# BUTTONS.net
KiCad netlist of a schematic drawn in Altium Designer
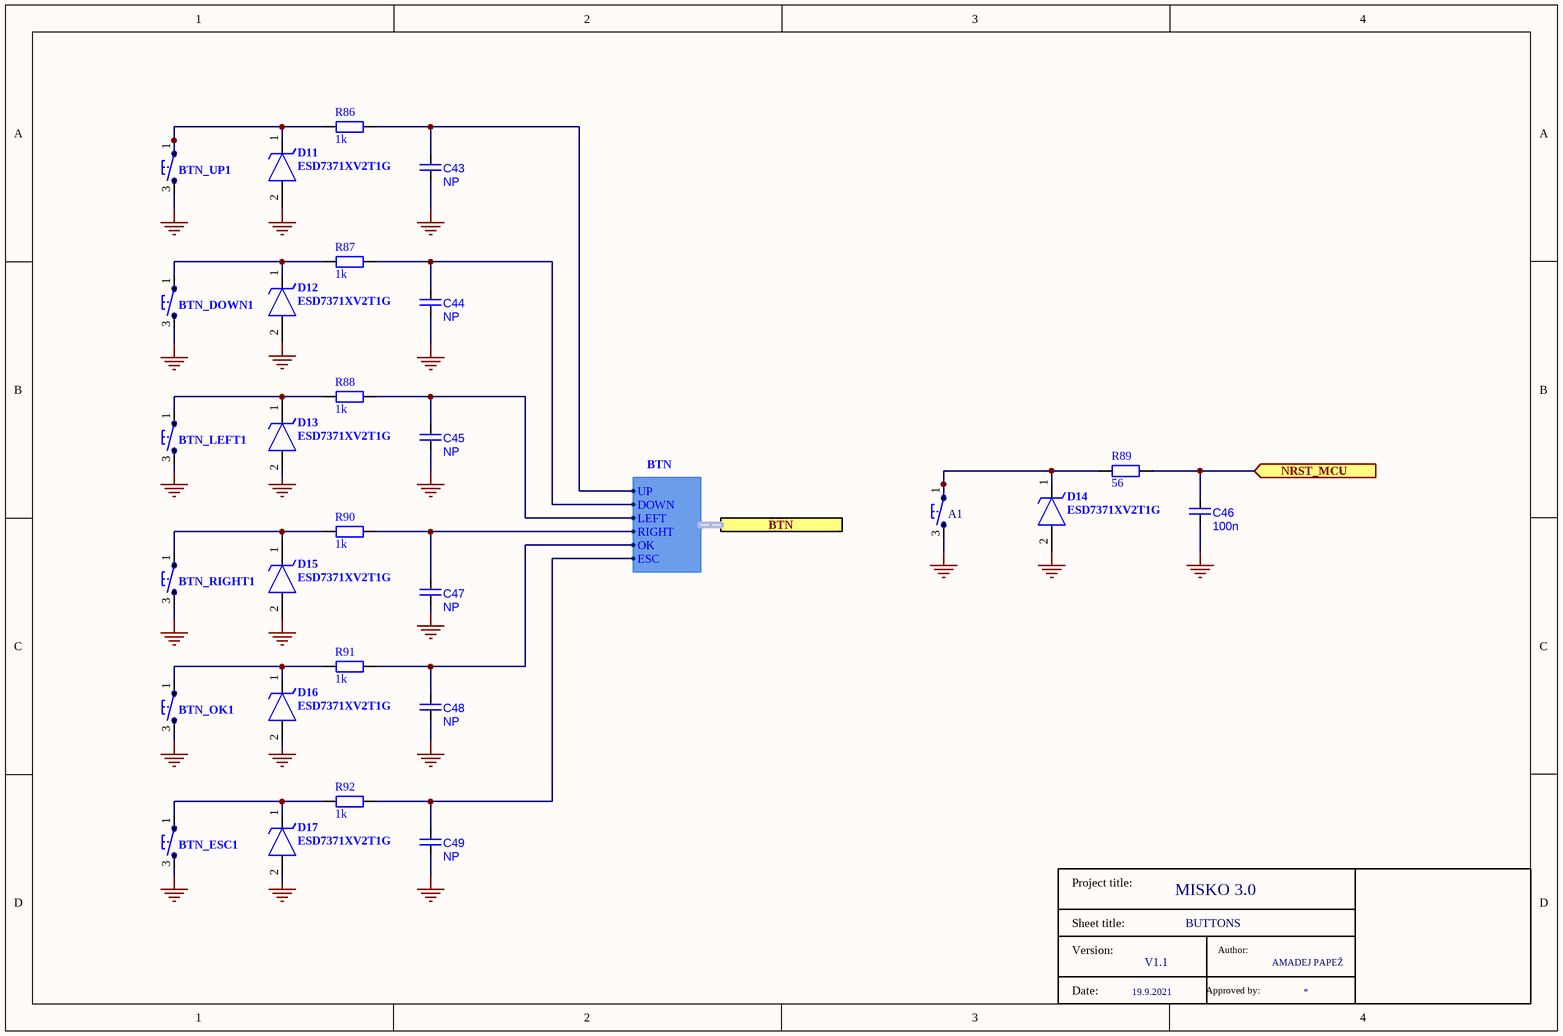
[diagram p0: BUTTONS.SchDoc]

(export (version "E")
  (design (tool "Eeschema 10.0.6"))
  (components
    (comp (ref "A1")
      (value "Button_6x6")
      (footprint "Tipka 6x6")
      (description "Tactile switch SMD")
      (libsource (lib "MISKO3_V6") (part "Button_6x6"))
    )
    (comp (ref "BTN_DOWN1")
      (value "Button_6x6")
      (footprint "Tipka 6x6")
      (description "Tactile switch SMD")
      (libsource (lib "MISKO3_V6") (part "Button_6x6"))
    )
    (comp (ref "BTN_ESC1")
      (value "Button_6x6")
      (footprint "Tipka 6x6")
      (description "Tactile switch SMD")
      (libsource (lib "MISKO3_V6") (part "Button_6x6"))
    )
    (comp (ref "BTN_LEFT1")
      (value "Button_6x6")
      (footprint "Tipka 6x6")
      (description "Tactile switch SMD")
      (libsource (lib "MISKO3_V6") (part "Button_6x6"))
    )
    (comp (ref "BTN_OK1")
      (value "Button_6x6")
      (footprint "Tipka 6x6")
      (description "Tactile switch SMD")
      (libsource (lib "MISKO3_V6") (part "Button_6x6"))
    )
    (comp (ref "BTN_RIGHT1")
      (value "Button_6x6")
      (footprint "Tipka 6x6")
      (description "Tactile switch SMD")
      (libsource (lib "MISKO3_V6") (part "Button_6x6"))
    )
    (comp (ref "BTN_UP1")
      (value "Button_6x6")
      (footprint "Tipka 6x6")
      (description "Tactile switch SMD")
      (libsource (lib "MISKO3_V6") (part "Button_6x6"))
    )
    (comp (ref "C43")
      (value "NP")
      (footprint "C0603")
      (description "Capacitor")
      (libsource (lib "MISKO3_V6") (part "C"))
    )
    (comp (ref "C44")
      (value "NP")
      (footprint "C0603")
      (description "Capacitor")
      (libsource (lib "MISKO3_V6") (part "C"))
    )
    (comp (ref "C45")
      (value "NP")
      (footprint "C0603")
      (description "Capacitor")
      (libsource (lib "MISKO3_V6") (part "C"))
    )
    (comp (ref "C46")
      (value "100n")
      (footprint "C0603")
      (description "Capacitor")
      (libsource (lib "MISKO3_V6") (part "C"))
    )
    (comp (ref "C47")
      (value "NP")
      (footprint "C0603")
      (description "Capacitor")
      (libsource (lib "MISKO3_V6") (part "C"))
    )
    (comp (ref "C48")
      (value "NP")
      (footprint "C0603")
      (description "Capacitor")
      (libsource (lib "MISKO3_V6") (part "C"))
    )
    (comp (ref "C49")
      (value "NP")
      (footprint "C0603")
      (description "Capacitor")
      (libsource (lib "MISKO3_V6") (part "C"))
    )
    (comp (ref "D11")
      (value "ESD7371XV2T1G")
      (footprint "SOD1608X70N")
      (description "TVS Diode (Uni-directional)")
      (fields (field (name "MOUSER PART NUMBER") "863-ESD7371XV2T1G"))
      (libsource (lib "MISKO3_V6") (part "ESD7371XV2T1G"))
    )
    (comp (ref "D12")
      (value "ESD7371XV2T1G")
      (footprint "SOD1608X70N")
      (description "TVS Diode (Uni-directional)")
      (fields (field (name "MOUSER PART NUMBER") "863-ESD7371XV2T1G"))
      (libsource (lib "MISKO3_V6") (part "ESD7371XV2T1G"))
    )
    (comp (ref "D13")
      (value "ESD7371XV2T1G")
      (footprint "SOD1608X70N")
      (description "TVS Diode (Uni-directional)")
      (fields (field (name "MOUSER PART NUMBER") "863-ESD7371XV2T1G"))
      (libsource (lib "MISKO3_V6") (part "ESD7371XV2T1G"))
    )
    (comp (ref "D14")
      (value "ESD7371XV2T1G")
      (footprint "SOD1608X70N")
      (description "TVS Diode (Uni-directional)")
      (fields (field (name "MOUSER PART NUMBER") "863-ESD7371XV2T1G"))
      (libsource (lib "MISKO3_V6") (part "ESD7371XV2T1G"))
    )
    (comp (ref "D15")
      (value "ESD7371XV2T1G")
      (footprint "SOD1608X70N")
      (description "TVS Diode (Uni-directional)")
      (fields (field (name "MOUSER PART NUMBER") "863-ESD7371XV2T1G"))
      (libsource (lib "MISKO3_V6") (part "ESD7371XV2T1G"))
    )
    (comp (ref "D16")
      (value "ESD7371XV2T1G")
      (footprint "SOD1608X70N")
      (description "TVS Diode (Uni-directional)")
      (fields (field (name "MOUSER PART NUMBER") "863-ESD7371XV2T1G"))
      (libsource (lib "MISKO3_V6") (part "ESD7371XV2T1G"))
    )
    (comp (ref "D17")
      (value "ESD7371XV2T1G")
      (footprint "SOD1608X70N")
      (description "TVS Diode (Uni-directional)")
      (fields (field (name "MOUSER PART NUMBER") "863-ESD7371XV2T1G"))
      (libsource (lib "MISKO3_V6") (part "ESD7371XV2T1G"))
    )
    (comp (ref "R86")
      (value "1k")
      (footprint "R1608_0603I_L")
      (description "R")
      (libsource (lib "MISKO3_V6") (part "R"))
    )
    (comp (ref "R87")
      (value "1k")
      (footprint "R1608_0603I_L")
      (description "R")
      (libsource (lib "MISKO3_V6") (part "R"))
    )
    (comp (ref "R88")
      (value "1k")
      (footprint "R1608_0603I_L")
      (description "R")
      (libsource (lib "MISKO3_V6") (part "R"))
    )
    (comp (ref "R89")
      (value "56")
      (footprint "R1608_0603I_L")
      (description "R")
      (libsource (lib "MISKO3_V6") (part "R"))
    )
    (comp (ref "R90")
      (value "1k")
      (footprint "R1608_0603I_L")
      (description "R")
      (libsource (lib "MISKO3_V6") (part "R"))
    )
    (comp (ref "R91")
      (value "1k")
      (footprint "R1608_0603I_L")
      (description "R")
      (libsource (lib "MISKO3_V6") (part "R"))
    )
    (comp (ref "R92")
      (value "1k")
      (footprint "R1608_0603I_L")
      (description "R")
      (libsource (lib "MISKO3_V6") (part "R"))
    )
    (comp (ref "T10") (value "~") (libsource (lib "MISKO3_V6") (part "Title block")))
  )
  (nets
    (net (code "2") (name "/NRST_MCU") (class "Default")
      (node (ref "C46") (pin "2") (pinfunction "2_2") (pintype "passive"))
      (node (ref "R89") (pin "1") (pintype "passive"))
    )
    (net (code "4") (name "GND") (class "Default")
      (node (ref "A1") (pin "3") (pinfunction "3_3") (pintype "passive"))
      (node (ref "BTN_DOWN1") (pin "3") (pinfunction "3_3") (pintype "passive"))
      (node (ref "BTN_ESC1") (pin "3") (pinfunction "3_3") (pintype "passive"))
      (node (ref "BTN_LEFT1") (pin "3") (pinfunction "3_3") (pintype "passive"))
      (node (ref "BTN_OK1") (pin "3") (pinfunction "3_3") (pintype "passive"))
      (node (ref "BTN_RIGHT1") (pin "3") (pinfunction "3_3") (pintype "passive"))
      (node (ref "BTN_UP1") (pin "3") (pinfunction "3_3") (pintype "passive"))
      (node (ref "C43") (pin "1") (pinfunction "1_1") (pintype "passive"))
      (node (ref "C44") (pin "1") (pinfunction "1_1") (pintype "passive"))
      (node (ref "C45") (pin "1") (pinfunction "1_1") (pintype "passive"))
      (node (ref "C46") (pin "1") (pinfunction "1_1") (pintype "passive"))
      (node (ref "C47") (pin "1") (pinfunction "1_1") (pintype "passive"))
      (node (ref "C48") (pin "1") (pinfunction "1_1") (pintype "passive"))
      (node (ref "C49") (pin "1") (pinfunction "1_1") (pintype "passive"))
      (node (ref "D11") (pin "2") (pinfunction "A_2") (pintype "passive"))
      (node (ref "D12") (pin "2") (pinfunction "A_2") (pintype "passive"))
      (node (ref "D13") (pin "2") (pinfunction "A_2") (pintype "passive"))
      (node (ref "D14") (pin "2") (pinfunction "A_2") (pintype "passive"))
      (node (ref "D15") (pin "2") (pinfunction "A_2") (pintype "passive"))
      (node (ref "D16") (pin "2") (pinfunction "A_2") (pintype "passive"))
      (node (ref "D17") (pin "2") (pinfunction "A_2") (pintype "passive"))
    )
    (net (code "5") (name "Net-(C43-Pad2)") (class "Default")
      (node (ref "C43") (pin "2") (pinfunction "2_2") (pintype "passive"))
      (node (ref "R86") (pin "1") (pintype "passive"))
    )
    (net (code "6") (name "Net-(C44-Pad2)") (class "Default")
      (node (ref "C44") (pin "2") (pinfunction "2_2") (pintype "passive"))
      (node (ref "R87") (pin "1") (pintype "passive"))
    )
    (net (code "7") (name "Net-(C45-Pad2)") (class "Default")
      (node (ref "C45") (pin "2") (pinfunction "2_2") (pintype "passive"))
      (node (ref "R88") (pin "1") (pintype "passive"))
    )
    (net (code "8") (name "Net-(C47-Pad2)") (class "Default")
      (node (ref "C47") (pin "2") (pinfunction "2_2") (pintype "passive"))
      (node (ref "R90") (pin "1") (pintype "passive"))
    )
    (net (code "9") (name "Net-(C48-Pad2)") (class "Default")
      (node (ref "C48") (pin "2") (pinfunction "2_2") (pintype "passive"))
      (node (ref "R91") (pin "1") (pintype "passive"))
    )
    (net (code "10") (name "Net-(C49-Pad2)") (class "Default")
      (node (ref "C49") (pin "2") (pinfunction "2_2") (pintype "passive"))
      (node (ref "R92") (pin "1") (pintype "passive"))
    )
    (net (code "11") (name "Net-(D11-K)") (class "Default")
      (node (ref "BTN_UP1") (pin "1") (pinfunction "1_1") (pintype "passive"))
      (node (ref "D11") (pin "1") (pinfunction "K_1") (pintype "passive"))
      (node (ref "R86") (pin "2") (pintype "passive"))
    )
    (net (code "12") (name "Net-(D12-K)") (class "Default")
      (node (ref "BTN_DOWN1") (pin "1") (pinfunction "1_1") (pintype "passive"))
      (node (ref "D12") (pin "1") (pinfunction "K_1") (pintype "passive"))
      (node (ref "R87") (pin "2") (pintype "passive"))
    )
    (net (code "13") (name "Net-(D13-K)") (class "Default")
      (node (ref "BTN_LEFT1") (pin "1") (pinfunction "1_1") (pintype "passive"))
      (node (ref "D13") (pin "1") (pinfunction "K_1") (pintype "passive"))
      (node (ref "R88") (pin "2") (pintype "passive"))
    )
    (net (code "14") (name "Net-(D14-K)") (class "Default")
      (node (ref "A1") (pin "1") (pinfunction "1_1") (pintype "passive"))
      (node (ref "D14") (pin "1") (pinfunction "K_1") (pintype "passive"))
      (node (ref "R89") (pin "2") (pintype "passive"))
    )
    (net (code "15") (name "Net-(D15-K)") (class "Default")
      (node (ref "BTN_RIGHT1") (pin "1") (pinfunction "1_1") (pintype "passive"))
      (node (ref "D15") (pin "1") (pinfunction "K_1") (pintype "passive"))
      (node (ref "R90") (pin "2") (pintype "passive"))
    )
    (net (code "16") (name "Net-(D16-K)") (class "Default")
      (node (ref "BTN_OK1") (pin "1") (pinfunction "1_1") (pintype "passive"))
      (node (ref "D16") (pin "1") (pinfunction "K_1") (pintype "passive"))
      (node (ref "R91") (pin "2") (pintype "passive"))
    )
    (net (code "17") (name "Net-(D17-K)") (class "Default")
      (node (ref "BTN_ESC1") (pin "1") (pinfunction "1_1") (pintype "passive"))
      (node (ref "D17") (pin "1") (pinfunction "K_1") (pintype "passive"))
      (node (ref "R92") (pin "2") (pintype "passive"))
    )
  )
)
